# interfaces.net
KiCad netlist of a schematic drawn in Altium Designer
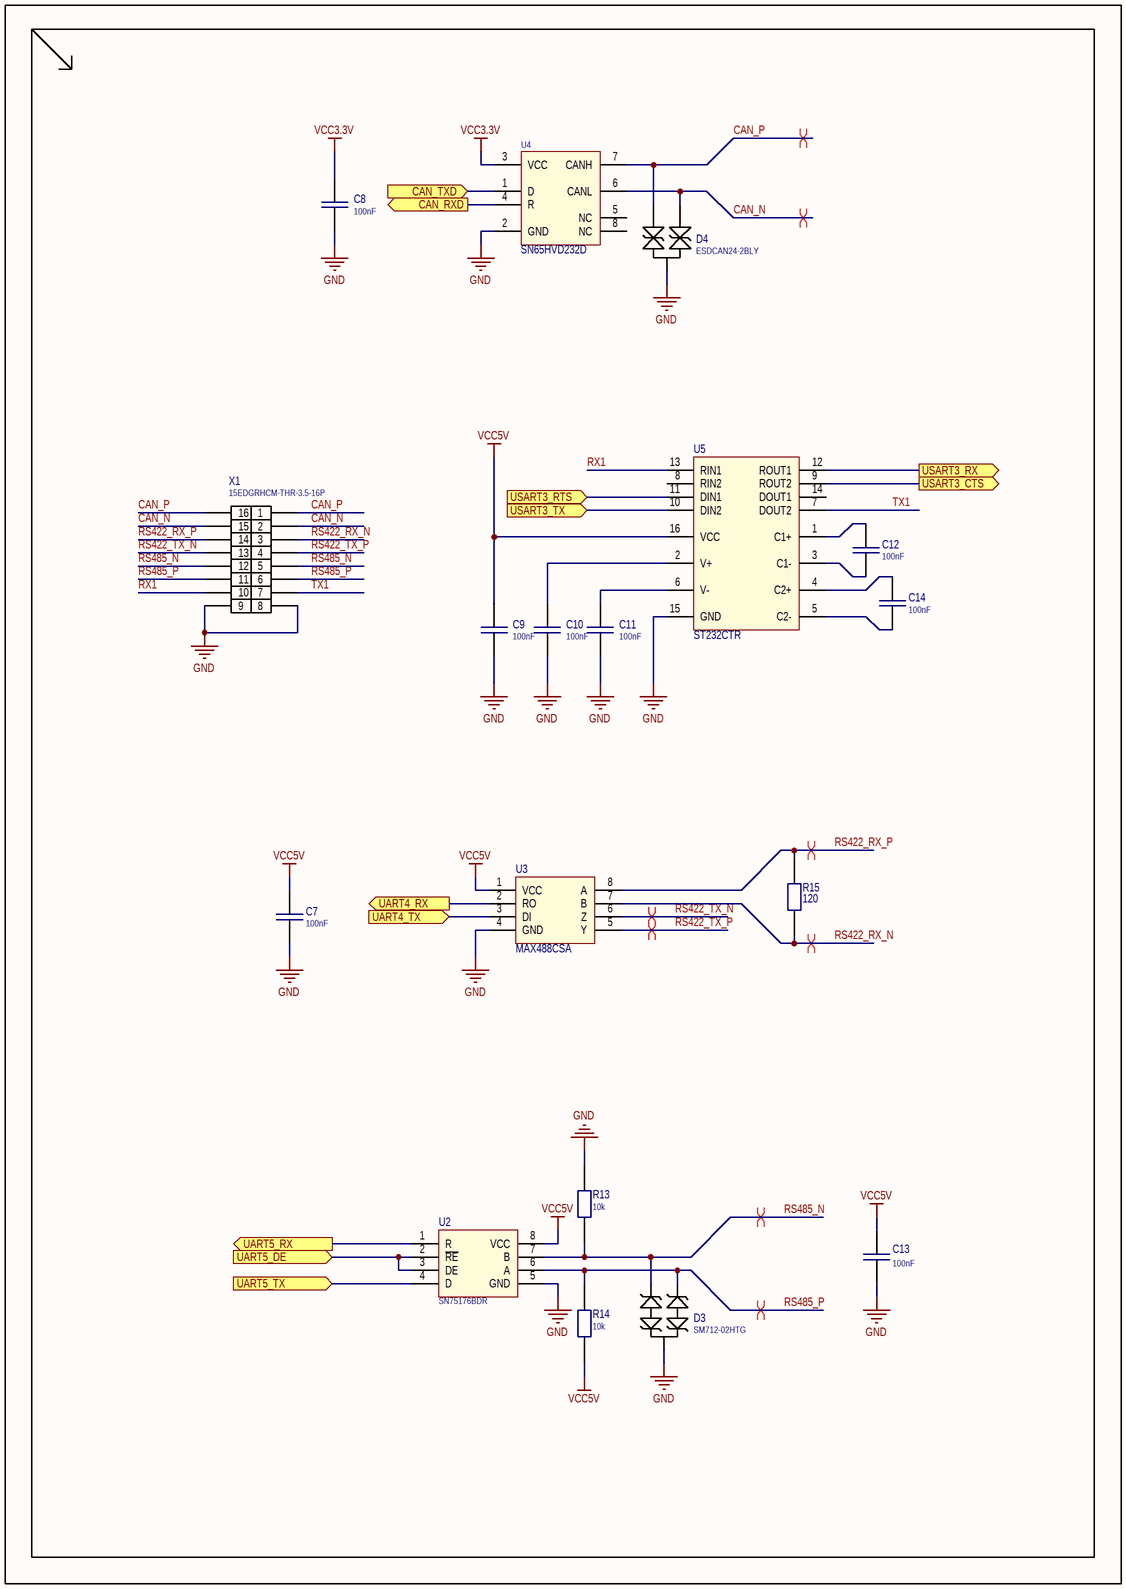
[diagram p0: interfaces.schdoc]

(export (version "E")
  (design (tool "Eeschema 10.0.6"))
  (components
    (comp (ref "C7")
      (value "100nF")
      (footprint "C_0603")
      (description "Capacitor")
      (fields (field (name "PART NUMBER") "CC0603JPX7R9BB104"))
      (libsource (lib "capacitors") (part "C0603"))
    )
    (comp (ref "C8")
      (value "100nF")
      (footprint "C_0603")
      (description "Capacitor")
      (fields (field (name "PART NUMBER") "CC0603JPX7R9BB104"))
      (libsource (lib "capacitors") (part "C0603"))
    )
    (comp (ref "C9")
      (value "100nF")
      (footprint "C_0603")
      (description "Capacitor")
      (fields (field (name "PART NUMBER") "CC0603JPX7R9BB104"))
      (libsource (lib "capacitors") (part "C0603"))
    )
    (comp (ref "C10")
      (value "100nF")
      (footprint "C_0603")
      (description "Capacitor")
      (fields (field (name "PART NUMBER") "CC0603JPX7R9BB104"))
      (libsource (lib "capacitors") (part "C0603"))
    )
    (comp (ref "C11")
      (value "100nF")
      (footprint "C_0603")
      (description "Capacitor")
      (fields (field (name "PART NUMBER") "CC0603JPX7R9BB104"))
      (libsource (lib "capacitors") (part "C0603"))
    )
    (comp (ref "C12")
      (value "100nF")
      (footprint "C_0603")
      (description "Capacitor")
      (fields (field (name "PART NUMBER") "CC0603JPX7R9BB104"))
      (libsource (lib "capacitors") (part "C0603"))
    )
    (comp (ref "C13")
      (value "100nF")
      (footprint "C_0603")
      (description "Capacitor")
      (fields (field (name "PART NUMBER") "CC0603JPX7R9BB104"))
      (libsource (lib "capacitors") (part "C0603"))
    )
    (comp (ref "C14")
      (value "100nF")
      (footprint "C_0603")
      (description "Capacitor")
      (fields (field (name "PART NUMBER") "CC0603JPX7R9BB104"))
      (libsource (lib "capacitors") (part "C0603"))
    )
    (comp (ref "D3")
      (value "SM712-02HTG")
      (footprint "diode:SOT23")
      (description "ESD")
      (libsource (lib "diode") (part "ESD"))
    )
    (comp (ref "D4")
      (value "ESDCAN24-2BLY")
      (footprint "diode:SOT23")
      (description "ESD")
      (libsource (lib "diode") (part "ESD_CAN"))
    )
    (comp (ref "R13")
      (value "10k")
      (footprint "R_0603")
      (description "Resistor")
      (fields (field (name "PART NUMBER") "RC0603FR-0710KL"))
      (libsource (lib "resistors") (part "RES_SMD"))
    )
    (comp (ref "R14")
      (value "10k")
      (footprint "R_0603")
      (description "Resistor")
      (fields (field (name "PART NUMBER") "RC0603FR-0710KL"))
      (libsource (lib "resistors") (part "RES_SMD"))
    )
    (comp (ref "R15")
      (value "120")
      (footprint "R_0603")
      (description "Resistor")
      (fields (field (name "PART NUMBER") "RC0603FR-07120RL"))
      (libsource (lib "resistors") (part "RES_SMD"))
    )
    (comp (ref "U2")
      (value "SN75176BDR")
      (footprint "SO-8")
      (description "RS485 Half Duplex Convertor")
      (libsource (lib "discret_ic") (part "SN75176BDR"))
    )
    (comp (ref "U3")
      (value "MAX488CSA")
      (footprint "discret_ic:SO-8_M")
      (description "RS485 Full Duplex Convertor")
      (libsource (lib "discret_ic") (part "ADM4855ARZ"))
    )
    (comp (ref "U4")
      (value "SN65HVD232D")
      (footprint "SO-8_M")
      (description "CAN_transiever")
      (fields (field (name "PART NUMBER") "SN65HVD232DR") (field (name "ALTERNATIVE PART") "XL1050"))
      (libsource (lib "discret_ic") (part "SN65HVD232D"))
    )
    (comp (ref "U5")
      (value "ST232CTR")
      (footprint "TSSOP16_STM")
      (description "No Description Available")
      (fields
        (field (name "ALTERNATIVE PART") "SP3232EEY-L/TR")
        (field (name "COPYRIGHT") "Copyright (C) 2022 Ultra Librarian. All rights reserved.")
      )
      (libsource (lib "discret_ic") (part "ST232CTR"))
    )
    (comp (ref "X1")
      (value "15EDGRHCM-THR-3.5-16P")
      (footprint "DMC 1,5/ 8-G1F-3,5-LR P20THR / 1787072")
      (libsource (lib "connectors_socets") (part "DMC 1,5/ 8-G1F-3,5-LR P20THR / 1787072"))
    )
  )
  (nets
    (net (code "1") (name "/CAN_N") (class "Default")
      (node (ref "D4") (pin "2") (pinfunction "2_2") (pintype "passive"))
      (node (ref "U4") (pin "6") (pinfunction "CANL_6") (pintype "passive"))
      (node (ref "X1") (pin "15") (pinfunction "15_15") (pintype "passive"))
      (node (ref "X1") (pin "2") (pinfunction "2_2") (pintype "passive"))
    )
    (net (code "2") (name "/CAN_P") (class "Default")
      (node (ref "D4") (pin "1") (pinfunction "1_1") (pintype "passive"))
      (node (ref "U4") (pin "7") (pinfunction "CANH_7") (pintype "passive"))
      (node (ref "X1") (pin "1") (pinfunction "1_1") (pintype "passive"))
      (node (ref "X1") (pin "16") (pinfunction "16_16") (pintype "passive"))
    )
    (net (code "3") (name "/CAN_RXD") (class "Default")
      (node (ref "U4") (pin "4") (pinfunction "R_4") (pintype "passive"))
    )
    (net (code "4") (name "/CAN_TXD") (class "Default")
      (node (ref "U4") (pin "1") (pinfunction "D_1") (pintype "passive"))
    )
    (net (code "5") (name "/RS422_RX_N") (class "Default")
      (node (ref "R15") (pin "2") (pinfunction "2_2") (pintype "passive"))
      (node (ref "U3") (pin "7") (pinfunction "B_7") (pintype "passive"))
      (node (ref "X1") (pin "3") (pinfunction "3_3") (pintype "passive"))
    )
    (net (code "6") (name "/RS422_RX_P") (class "Default")
      (node (ref "R15") (pin "1") (pinfunction "1_1") (pintype "passive"))
      (node (ref "U3") (pin "8") (pinfunction "A_8") (pintype "passive"))
      (node (ref "X1") (pin "14") (pinfunction "14_14") (pintype "passive"))
    )
    (net (code "7") (name "/RS422_TX_N") (class "Default")
      (node (ref "U3") (pin "6") (pinfunction "Z_6") (pintype "passive"))
      (node (ref "X1") (pin "13") (pinfunction "13_13") (pintype "passive"))
    )
    (net (code "8") (name "/RS422_TX_P") (class "Default")
      (node (ref "U3") (pin "5") (pinfunction "Y_5") (pintype "passive"))
      (node (ref "X1") (pin "4") (pinfunction "4_4") (pintype "passive"))
    )
    (net (code "9") (name "/RS485_N") (class "Default")
      (node (ref "D3") (pin "1") (pinfunction "1_1") (pintype "passive"))
      (node (ref "R13") (pin "1") (pinfunction "1_1") (pintype "passive"))
      (node (ref "U2") (pin "7") (pinfunction "B_7") (pintype "passive"))
      (node (ref "X1") (pin "12") (pinfunction "12_12") (pintype "passive"))
      (node (ref "X1") (pin "5") (pinfunction "5_5") (pintype "passive"))
    )
    (net (code "10") (name "/RS485_P") (class "Default")
      (node (ref "D3") (pin "2") (pinfunction "2_2") (pintype "passive"))
      (node (ref "R14") (pin "2") (pinfunction "2_2") (pintype "passive"))
      (node (ref "U2") (pin "6") (pinfunction "A_6") (pintype "passive"))
      (node (ref "X1") (pin "11") (pinfunction "11_11") (pintype "passive"))
      (node (ref "X1") (pin "6") (pinfunction "6_6") (pintype "passive"))
    )
    (net (code "11") (name "/RX1") (class "Default")
      (node (ref "U5") (pin "13") (pinfunction "RIN1_13") (pintype "passive"))
      (node (ref "X1") (pin "10") (pinfunction "10_10") (pintype "passive"))
    )
    (net (code "12") (name "/TX1") (class "Default")
      (node (ref "U5") (pin "7") (pinfunction "DOUT2_7") (pintype "passive"))
      (node (ref "X1") (pin "7") (pinfunction "7_7") (pintype "passive"))
    )
    (net (code "13") (name "/UART4_RX") (class "Default")
      (node (ref "U3") (pin "2") (pinfunction "RO_2") (pintype "passive"))
    )
    (net (code "14") (name "/UART4_TX") (class "Default")
      (node (ref "U3") (pin "3") (pinfunction "DI_3") (pintype "passive"))
    )
    (net (code "15") (name "/UART5_DE") (class "Default")
      (node (ref "U2") (pin "2") (pinfunction "~{RE}_2") (pintype "passive"))
      (node (ref "U2") (pin "3") (pinfunction "DE_3") (pintype "passive"))
    )
    (net (code "16") (name "/UART5_RX") (class "Default")
      (node (ref "U2") (pin "1") (pinfunction "R_1") (pintype "passive"))
    )
    (net (code "17") (name "/UART5_TX") (class "Default")
      (node (ref "U2") (pin "4") (pinfunction "D_4") (pintype "passive"))
    )
    (net (code "18") (name "/USART3_CTS") (class "Default")
      (node (ref "U5") (pin "9") (pinfunction "ROUT2_9") (pintype "passive"))
    )
    (net (code "19") (name "/USART3_RTS") (class "Default")
      (node (ref "U5") (pin "11") (pinfunction "DIN1_11") (pintype "passive"))
    )
    (net (code "20") (name "/USART3_RX") (class "Default")
      (node (ref "U5") (pin "12") (pinfunction "ROUT1_12") (pintype "passive"))
    )
    (net (code "21") (name "/USART3_TX") (class "Default")
      (node (ref "U5") (pin "10") (pinfunction "DIN2_10") (pintype "passive"))
    )
    (net (code "22") (name "GND") (class "Default")
      (node (ref "C10") (pin "1") (pinfunction "1_1") (pintype "passive"))
      (node (ref "C11") (pin "1") (pinfunction "1_1") (pintype "passive"))
      (node (ref "C13") (pin "1") (pinfunction "1_1") (pintype "passive"))
      (node (ref "C7") (pin "1") (pinfunction "1_1") (pintype "passive"))
      (node (ref "C8") (pin "1") (pinfunction "1_1") (pintype "passive"))
      (node (ref "C9") (pin "1") (pinfunction "1_1") (pintype "passive"))
      (node (ref "D3") (pin "3") (pinfunction "3_3") (pintype "passive"))
      (node (ref "D4") (pin "3") (pinfunction "3_3") (pintype "passive"))
      (node (ref "R13") (pin "2") (pinfunction "2_2") (pintype "passive"))
      (node (ref "U2") (pin "5") (pinfunction "GND_5") (pintype "passive"))
      (node (ref "U3") (pin "4") (pinfunction "GND_4") (pintype "passive"))
      (node (ref "U4") (pin "2") (pinfunction "GND_2") (pintype "passive"))
      (node (ref "U5") (pin "15") (pinfunction "GND_15") (pintype "passive"))
      (node (ref "X1") (pin "8") (pinfunction "8_8") (pintype "passive"))
      (node (ref "X1") (pin "9") (pinfunction "9_9") (pintype "passive"))
    )
    (net (code "23") (name "Net-(U5-C1+)") (class "Default")
      (node (ref "C12") (pin "1") (pinfunction "1_1") (pintype "passive"))
      (node (ref "U5") (pin "1") (pinfunction "C1+_1") (pintype "passive"))
    )
    (net (code "24") (name "Net-(U5-C1-)") (class "Default")
      (node (ref "C12") (pin "2") (pinfunction "2_2") (pintype "passive"))
      (node (ref "U5") (pin "3") (pinfunction "C1-_3") (pintype "passive"))
    )
    (net (code "25") (name "Net-(U5-C2+)") (class "Default")
      (node (ref "C14") (pin "1") (pinfunction "1_1") (pintype "passive"))
      (node (ref "U5") (pin "4") (pinfunction "C2+_4") (pintype "passive"))
    )
    (net (code "26") (name "Net-(U5-C2-)") (class "Default")
      (node (ref "C14") (pin "2") (pinfunction "2_2") (pintype "passive"))
      (node (ref "U5") (pin "5") (pinfunction "C2-_5") (pintype "passive"))
    )
    (net (code "27") (name "Net-(U5-V+)") (class "Default")
      (node (ref "C10") (pin "2") (pinfunction "2_2") (pintype "passive"))
      (node (ref "U5") (pin "2") (pinfunction "V+_2") (pintype "passive"))
    )
    (net (code "28") (name "Net-(U5-V-)") (class "Default")
      (node (ref "C11") (pin "2") (pinfunction "2_2") (pintype "passive"))
      (node (ref "U5") (pin "6") (pinfunction "V-_6") (pintype "passive"))
    )
    (net (code "29") (name "VCC3.3V") (class "Default")
      (node (ref "C8") (pin "2") (pinfunction "2_2") (pintype "passive"))
      (node (ref "U4") (pin "3") (pinfunction "VCC_3") (pintype "passive"))
    )
    (net (code "30") (name "VCC5V") (class "Default")
      (node (ref "C13") (pin "2") (pinfunction "2_2") (pintype "passive"))
      (node (ref "C7") (pin "2") (pinfunction "2_2") (pintype "passive"))
      (node (ref "C9") (pin "2") (pinfunction "2_2") (pintype "passive"))
      (node (ref "R14") (pin "1") (pinfunction "1_1") (pintype "passive"))
      (node (ref "U2") (pin "8") (pinfunction "VCC_8") (pintype "passive"))
      (node (ref "U3") (pin "1") (pinfunction "VCC_1") (pintype "passive"))
      (node (ref "U5") (pin "16") (pinfunction "VCC_16") (pintype "passive"))
    )
    (net (code "31") (name "unconnected-(U4-NC-Pad5)") (class "Default")
      (node (ref "U4") (pin "5") (pinfunction "NC_5") (pintype "passive"))
    )
    (net (code "32") (name "unconnected-(U4-NC-Pad8)") (class "Default")
      (node (ref "U4") (pin "8") (pinfunction "NC_8") (pintype "passive"))
    )
    (net (code "33") (name "unconnected-(U5-DOUT1-Pad14)") (class "Default")
      (node (ref "U5") (pin "14") (pinfunction "DOUT1_14") (pintype "passive"))
    )
    (net (code "34") (name "unconnected-(U5-RIN2-Pad8)") (class "Default")
      (node (ref "U5") (pin "8") (pinfunction "RIN2_8") (pintype "passive"))
    )
  )
)
